# ET-POWER.net
KiCad netlist of a schematic drawn in Altium Designer
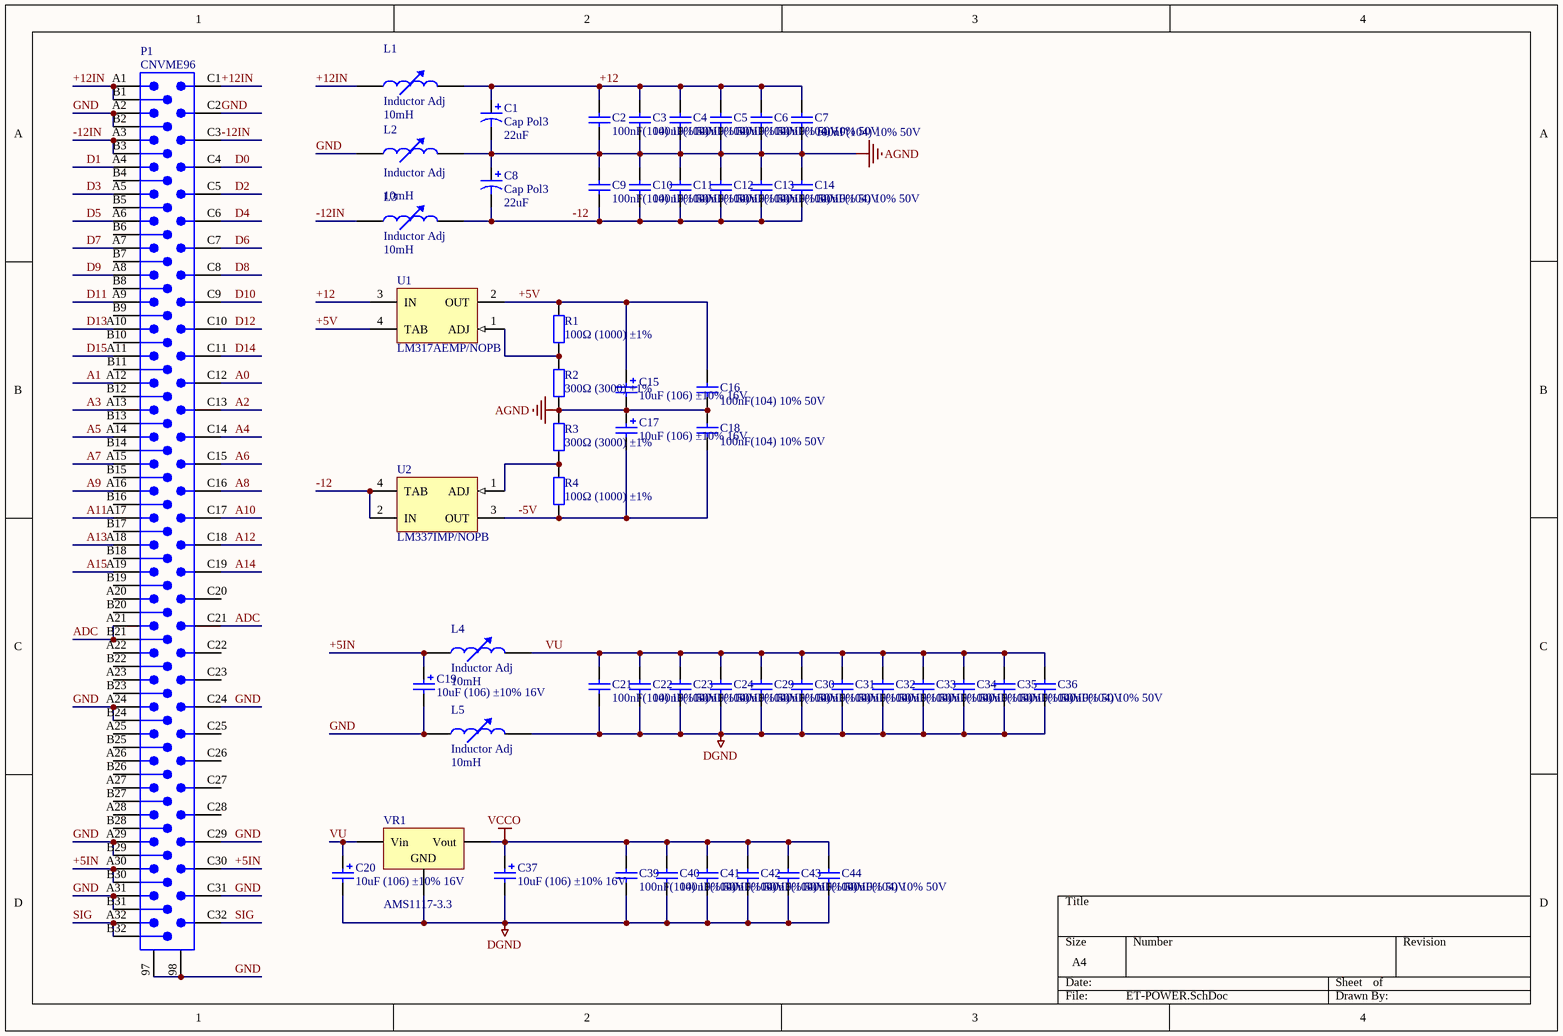
[diagram p0: ET-POWER.SchDoc]

(export (version "E")
  (design (tool "Eeschema 10.0.6"))
  (components
    (comp (ref "C1")
      (value "Cap Pol3")
      (footprint "2220")
      (description "Polarized Capacitor (Surface Mount)")
      (fields (field (name "ALTIUM_VALUE") "22uF") (field (name "PUBLISHER") "Altium Limited"))
      (libsource (lib "Miscellaneous Devices") (part "Cap Pol3"))
    )
    (comp (ref "C2")
      (value "100nF(104) 10% 50V")
      (footprint "LC-0805_C")
      (description "贴片电容")
      (libsource (lib "Miscellaneous Devices LC") (part "0805 100nF(104) 10% 50V"))
    )
    (comp (ref "C3")
      (value "100nF(104) 10% 50V")
      (footprint "LC-0805_C")
      (description "贴片电容")
      (libsource (lib "Miscellaneous Devices LC") (part "0805 100nF(104) 10% 50V"))
    )
    (comp (ref "C4")
      (value "100nF(104) 10% 50V")
      (footprint "LC-0805_C")
      (description "贴片电容")
      (libsource (lib "Miscellaneous Devices LC") (part "0805 100nF(104) 10% 50V"))
    )
    (comp (ref "C5")
      (value "100nF(104) 10% 50V")
      (footprint "LC-0805_C")
      (description "贴片电容")
      (libsource (lib "Miscellaneous Devices LC") (part "0805 100nF(104) 10% 50V"))
    )
    (comp (ref "C6")
      (value "100nF(104) 10% 50V")
      (footprint "LC-0805_C")
      (description "贴片电容")
      (libsource (lib "Miscellaneous Devices LC") (part "0805 100nF(104) 10% 50V"))
    )
    (comp (ref "C7")
      (value "100nF(104) 10% 50V")
      (footprint "LC-0805_C")
      (description "贴片电容")
      (libsource (lib "Miscellaneous Devices LC") (part "0805 100nF(104) 10% 50V"))
    )
    (comp (ref "C8")
      (value "Cap Pol3")
      (footprint "2220")
      (description "Polarized Capacitor (Surface Mount)")
      (fields (field (name "ALTIUM_VALUE") "22uF") (field (name "PUBLISHER") "Altium Limited"))
      (libsource (lib "Miscellaneous Devices") (part "Cap Pol3"))
    )
    (comp (ref "C9")
      (value "100nF(104) 10% 50V")
      (footprint "LC-0805_C")
      (description "贴片电容")
      (libsource (lib "Miscellaneous Devices LC") (part "0805 100nF(104) 10% 50V"))
    )
    (comp (ref "C10")
      (value "100nF(104) 10% 50V")
      (footprint "LC-0805_C")
      (description "贴片电容")
      (libsource (lib "Miscellaneous Devices LC") (part "0805 100nF(104) 10% 50V"))
    )
    (comp (ref "C11")
      (value "100nF(104) 10% 50V")
      (footprint "LC-0805_C")
      (description "贴片电容")
      (libsource (lib "Miscellaneous Devices LC") (part "0805 100nF(104) 10% 50V"))
    )
    (comp (ref "C12")
      (value "100nF(104) 10% 50V")
      (footprint "LC-0805_C")
      (description "贴片电容")
      (libsource (lib "Miscellaneous Devices LC") (part "0805 100nF(104) 10% 50V"))
    )
    (comp (ref "C13")
      (value "100nF(104) 10% 50V")
      (footprint "LC-0805_C")
      (description "贴片电容")
      (libsource (lib "Miscellaneous Devices LC") (part "0805 100nF(104) 10% 50V"))
    )
    (comp (ref "C14")
      (value "100nF(104) 10% 50V")
      (footprint "LC-0805_C")
      (description "贴片电容")
      (libsource (lib "Miscellaneous Devices LC") (part "0805 100nF(104) 10% 50V"))
    )
    (comp (ref "C15")
      (value "10uF (106) ±10% 16V")
      (footprint "LC-CASE-A_3216")
      (description "钽电容")
      (libsource (lib "Miscellaneous Devices LC") (part "3216 10uF (106) 10% 16V"))
    )
    (comp (ref "C16")
      (value "100nF(104) 10% 50V")
      (footprint "LC-0805_C")
      (description "贴片电容")
      (libsource (lib "Miscellaneous Devices LC") (part "0805 100nF(104) 10% 50V"))
    )
    (comp (ref "C17")
      (value "10uF (106) ±10% 16V")
      (footprint "LC-CASE-A_3216")
      (description "钽电容")
      (libsource (lib "Miscellaneous Devices LC") (part "3216 10uF (106) 10% 16V"))
    )
    (comp (ref "C18")
      (value "100nF(104) 10% 50V")
      (footprint "LC-0805_C")
      (description "贴片电容")
      (libsource (lib "Miscellaneous Devices LC") (part "0805 100nF(104) 10% 50V"))
    )
    (comp (ref "C19")
      (value "10uF (106) ±10% 16V")
      (footprint "LC-CASE-A_3216")
      (description "钽电容")
      (libsource (lib "Miscellaneous Devices LC") (part "3216 10uF (106) 10% 16V"))
    )
    (comp (ref "C20")
      (value "10uF (106) ±10% 16V")
      (footprint "LC-CASE-A_3216")
      (description "钽电容")
      (libsource (lib "Miscellaneous Devices LC") (part "3216 10uF (106) 10% 16V"))
    )
    (comp (ref "C21")
      (value "100nF(104) 10% 50V")
      (footprint "LC-0805_C")
      (description "贴片电容")
      (libsource (lib "Miscellaneous Devices LC") (part "0805 100nF(104) 10% 50V"))
    )
    (comp (ref "C22")
      (value "100nF(104) 10% 50V")
      (footprint "LC-0805_C")
      (description "贴片电容")
      (libsource (lib "Miscellaneous Devices LC") (part "0805 100nF(104) 10% 50V"))
    )
    (comp (ref "C23")
      (value "100nF(104) 10% 50V")
      (footprint "LC-0805_C")
      (description "贴片电容")
      (libsource (lib "Miscellaneous Devices LC") (part "0805 100nF(104) 10% 50V"))
    )
    (comp (ref "C24")
      (value "100nF(104) 10% 50V")
      (footprint "LC-0805_C")
      (description "贴片电容")
      (libsource (lib "Miscellaneous Devices LC") (part "0805 100nF(104) 10% 50V"))
    )
    (comp (ref "C29")
      (value "100nF(104) 10% 50V")
      (footprint "LC-0805_C")
      (description "贴片电容")
      (libsource (lib "Miscellaneous Devices LC") (part "0805 100nF(104) 10% 50V"))
    )
    (comp (ref "C30")
      (value "100nF(104) 10% 50V")
      (footprint "LC-0805_C")
      (description "贴片电容")
      (libsource (lib "Miscellaneous Devices LC") (part "0805 100nF(104) 10% 50V"))
    )
    (comp (ref "C31")
      (value "100nF(104) 10% 50V")
      (footprint "LC-0805_C")
      (description "贴片电容")
      (libsource (lib "Miscellaneous Devices LC") (part "0805 100nF(104) 10% 50V"))
    )
    (comp (ref "C32")
      (value "100nF(104) 10% 50V")
      (footprint "LC-0805_C")
      (description "贴片电容")
      (libsource (lib "Miscellaneous Devices LC") (part "0805 100nF(104) 10% 50V"))
    )
    (comp (ref "C33")
      (value "100nF(104) 10% 50V")
      (footprint "LC-0805_C")
      (description "贴片电容")
      (libsource (lib "Miscellaneous Devices LC") (part "0805 100nF(104) 10% 50V"))
    )
    (comp (ref "C34")
      (value "100nF(104) 10% 50V")
      (footprint "LC-0805_C")
      (description "贴片电容")
      (libsource (lib "Miscellaneous Devices LC") (part "0805 100nF(104) 10% 50V"))
    )
    (comp (ref "C35")
      (value "100nF(104) 10% 50V")
      (footprint "LC-0805_C")
      (description "贴片电容")
      (libsource (lib "Miscellaneous Devices LC") (part "0805 100nF(104) 10% 50V"))
    )
    (comp (ref "C36")
      (value "100nF(104) 10% 50V")
      (footprint "LC-0805_C")
      (description "贴片电容")
      (libsource (lib "Miscellaneous Devices LC") (part "0805 100nF(104) 10% 50V"))
    )
    (comp (ref "C37")
      (value "10uF (106) ±10% 16V")
      (footprint "LC-CASE-A_3216")
      (description "钽电容")
      (libsource (lib "Miscellaneous Devices LC") (part "3216 10uF (106) 10% 16V"))
    )
    (comp (ref "C39")
      (value "100nF(104) 10% 50V")
      (footprint "LC-0805_C")
      (description "贴片电容")
      (libsource (lib "Miscellaneous Devices LC") (part "0805 100nF(104) 10% 50V"))
    )
    (comp (ref "C40")
      (value "100nF(104) 10% 50V")
      (footprint "LC-0805_C")
      (description "贴片电容")
      (libsource (lib "Miscellaneous Devices LC") (part "0805 100nF(104) 10% 50V"))
    )
    (comp (ref "C41")
      (value "100nF(104) 10% 50V")
      (footprint "LC-0805_C")
      (description "贴片电容")
      (libsource (lib "Miscellaneous Devices LC") (part "0805 100nF(104) 10% 50V"))
    )
    (comp (ref "C42")
      (value "100nF(104) 10% 50V")
      (footprint "LC-0805_C")
      (description "贴片电容")
      (libsource (lib "Miscellaneous Devices LC") (part "0805 100nF(104) 10% 50V"))
    )
    (comp (ref "C43")
      (value "100nF(104) 10% 50V")
      (footprint "LC-0805_C")
      (description "贴片电容")
      (libsource (lib "Miscellaneous Devices LC") (part "0805 100nF(104) 10% 50V"))
    )
    (comp (ref "C44")
      (value "100nF(104) 10% 50V")
      (footprint "LC-0805_C")
      (description "贴片电容")
      (libsource (lib "Miscellaneous Devices LC") (part "0805 100nF(104) 10% 50V"))
    )
    (comp (ref "L1")
      (value "Inductor Adj")
      (footprint "AXIAL-0.4")
      (description "Adjustable Inductor")
      (fields (field (name "ALTIUM_VALUE") "10mH") (field (name "PUBLISHER") "Altium Limited"))
      (libsource (lib "Miscellaneous Devices") (part "Inductor Adj"))
    )
    (comp (ref "L2")
      (value "Inductor Adj")
      (footprint "AXIAL-0.4")
      (description "Adjustable Inductor")
      (fields (field (name "ALTIUM_VALUE") "10mH") (field (name "PUBLISHER") "Altium Limited"))
      (libsource (lib "Miscellaneous Devices") (part "Inductor Adj"))
    )
    (comp (ref "L3")
      (value "Inductor Adj")
      (footprint "AXIAL-0.4")
      (description "Adjustable Inductor")
      (fields (field (name "ALTIUM_VALUE") "10mH") (field (name "PUBLISHER") "Altium Limited"))
      (libsource (lib "Miscellaneous Devices") (part "Inductor Adj"))
    )
    (comp (ref "L4")
      (value "Inductor Adj")
      (footprint "AXIAL-0.4")
      (description "Adjustable Inductor")
      (fields (field (name "ALTIUM_VALUE") "10mH") (field (name "PUBLISHER") "Altium Limited"))
      (libsource (lib "Miscellaneous Devices") (part "Inductor Adj"))
    )
    (comp (ref "L5")
      (value "Inductor Adj")
      (footprint "AXIAL-0.4")
      (description "Adjustable Inductor")
      (fields (field (name "ALTIUM_VALUE") "10mH") (field (name "PUBLISHER") "Altium Limited"))
      (libsource (lib "Miscellaneous Devices") (part "Inductor Adj"))
    )
    (comp (ref "P1")
      (value "CNVME96")
      (footprint "mini-ET:CNVME96")
      (description "96-Pin Connector (3x32 2.54mm grid)")
      (libsource (lib "*") (part "CNVME96"))
    )
    (comp (ref "R1")
      (value "100Ω (1000) ±1%")
      (footprint "LC-0805_R")
      (description "贴片电阻")
      (libsource (lib "Miscellaneous Devices LC") (part "0805 100Ω (1000) 1%"))
    )
    (comp (ref "R2")
      (value "300Ω (3000) ±1%")
      (footprint "LC-0805_R")
      (description "贴片电阻")
      (libsource (lib "Miscellaneous Devices LC") (part "0805 300Ω (3000) 1%"))
    )
    (comp (ref "R3")
      (value "300Ω (3000) ±1%")
      (footprint "LC-0805_R")
      (description "贴片电阻")
      (libsource (lib "Miscellaneous Devices LC") (part "0805 300Ω (3000) 1%"))
    )
    (comp (ref "R4")
      (value "100Ω (1000) ±1%")
      (footprint "LC-0805_R")
      (description "贴片电阻")
      (libsource (lib "Miscellaneous Devices LC") (part "0805 100Ω (1000) 1%"))
    )
    (comp (ref "U1")
      (value "LM317AEMP/NOPB")
      (footprint "mini-ET:MP04A_N")
      (description "3-Terminal Adjustable Regulator, 4-pin SOT-223, Pb-Free")
      (fields (field (name "MANUFACTURER") "National Semiconductor"))
      (libsource (lib "National Semiconductor LDO") (part "LM317AEMP/NOPB"))
    )
    (comp (ref "U2")
      (value "LM337IMP/NOPB")
      (footprint "mini-ET:MP04A_N")
      (description "3-Terminal Adjustable Negative Regulator, 4-pin SOT-223, Pb-Free")
      (fields
        (field (name "MANUFACTURER") "National Semiconductor")
        (field (name "PUBLISHER") "Altium Limited")
      )
      (libsource (lib "NSC LDO") (part "LM337IMP/NOPB"))
    )
    (comp (ref "VR1")
      (value "AMS1117-3.3")
      (footprint "LC-SOT-223")
      (description "低压差线性稳压(LDO)")
      (libsource (lib "Miscellaneous Devices LC") (part "SOT-223 AMS1117-3.3"))
    )
  )
  (nets
    (net (code "1") (name "/+5IN") (class "Default")
      (node (ref "C19") (pin "1") (pinfunction "1_1") (pintype "passive"))
      (node (ref "L4") (pin "1") (pinfunction "1_1") (pintype "passive"))
      (node (ref "P1") (pin "A30") (pinfunction "A30_A30") (pintype "passive"))
      (node (ref "P1") (pin "B30") (pinfunction "B30_B30") (pintype "passive"))
      (node (ref "P1") (pin "C30") (pinfunction "C30_C30") (pintype "passive"))
    )
    (net (code "2") (name "/+5V") (class "Default")
      (node (ref "C15") (pin "1") (pinfunction "1_1") (pintype "passive"))
      (node (ref "C16") (pin "2") (pinfunction "2_2") (pintype "passive"))
      (node (ref "R1") (pin "2") (pinfunction "2_2") (pintype "passive"))
      (node (ref "U1") (pin "2") (pinfunction "OUT_2") (pintype "power_in"))
      (node (ref "U1") (pin "4") (pinfunction "TAB_4") (pintype "power_in"))
    )
    (net (code "3") (name "/+12") (class "Default")
      (node (ref "C1") (pin "1") (pinfunction "1_1") (pintype "passive"))
      (node (ref "C2") (pin "2") (pinfunction "2_2") (pintype "passive"))
      (node (ref "C3") (pin "2") (pinfunction "2_2") (pintype "passive"))
      (node (ref "C4") (pin "2") (pinfunction "2_2") (pintype "passive"))
      (node (ref "C5") (pin "2") (pinfunction "2_2") (pintype "passive"))
      (node (ref "C6") (pin "2") (pinfunction "2_2") (pintype "passive"))
      (node (ref "C7") (pin "2") (pinfunction "2_2") (pintype "passive"))
      (node (ref "L1") (pin "2") (pinfunction "2_2") (pintype "passive"))
      (node (ref "U1") (pin "3") (pinfunction "IN_3") (pintype "power_in"))
    )
    (net (code "4") (name "/+12IN") (class "Default")
      (node (ref "L1") (pin "1") (pinfunction "1_1") (pintype "passive"))
      (node (ref "P1") (pin "A1") (pinfunction "A1_A1") (pintype "passive"))
      (node (ref "P1") (pin "B1") (pinfunction "B1_B1") (pintype "passive"))
      (node (ref "P1") (pin "C1") (pinfunction "C1_C1") (pintype "passive"))
    )
    (net (code "5") (name "/-5V") (class "Default")
      (node (ref "C17") (pin "2") (pinfunction "2_2") (pintype "passive"))
      (node (ref "C18") (pin "1") (pinfunction "1_1") (pintype "passive"))
      (node (ref "R4") (pin "1") (pinfunction "1_1") (pintype "passive"))
      (node (ref "U2") (pin "3") (pinfunction "OUT_3") (pintype "power_in"))
    )
    (net (code "6") (name "/-12") (class "Default")
      (node (ref "C10") (pin "1") (pinfunction "1_1") (pintype "passive"))
      (node (ref "C11") (pin "1") (pinfunction "1_1") (pintype "passive"))
      (node (ref "C12") (pin "1") (pinfunction "1_1") (pintype "passive"))
      (node (ref "C13") (pin "1") (pinfunction "1_1") (pintype "passive"))
      (node (ref "C14") (pin "1") (pinfunction "1_1") (pintype "passive"))
      (node (ref "C8") (pin "2") (pinfunction "2_2") (pintype "passive"))
      (node (ref "C9") (pin "1") (pinfunction "1_1") (pintype "passive"))
      (node (ref "L3") (pin "2") (pinfunction "2_2") (pintype "passive"))
      (node (ref "U2") (pin "2") (pinfunction "IN_2") (pintype "power_in"))
      (node (ref "U2") (pin "4") (pinfunction "TAB_4") (pintype "power_in"))
    )
    (net (code "7") (name "/-12IN") (class "Default")
      (node (ref "L3") (pin "1") (pinfunction "1_1") (pintype "passive"))
      (node (ref "P1") (pin "A3") (pinfunction "A3_A3") (pintype "passive"))
      (node (ref "P1") (pin "B3") (pinfunction "B3_B3") (pintype "passive"))
      (node (ref "P1") (pin "C3") (pinfunction "C3_C3") (pintype "passive"))
    )
    (net (code "8") (name "/A0") (class "Default")
      (node (ref "P1") (pin "C12") (pinfunction "C12_C12") (pintype "passive"))
    )
    (net (code "9") (name "/A1") (class "Default")
      (node (ref "P1") (pin "A12") (pinfunction "A12_A12") (pintype "passive"))
    )
    (net (code "10") (name "/A2") (class "Default")
      (node (ref "P1") (pin "C13") (pinfunction "C13_C13") (pintype "passive"))
    )
    (net (code "11") (name "/A3") (class "Default")
      (node (ref "P1") (pin "A13") (pinfunction "A13_A13") (pintype "passive"))
    )
    (net (code "12") (name "/A4") (class "Default")
      (node (ref "P1") (pin "C14") (pinfunction "C14_C14") (pintype "passive"))
    )
    (net (code "13") (name "/A5") (class "Default")
      (node (ref "P1") (pin "A14") (pinfunction "A14_A14") (pintype "passive"))
    )
    (net (code "14") (name "/A6") (class "Default")
      (node (ref "P1") (pin "C15") (pinfunction "C15_C15") (pintype "passive"))
    )
    (net (code "15") (name "/A7") (class "Default")
      (node (ref "P1") (pin "A15") (pinfunction "A15_A15") (pintype "passive"))
    )
    (net (code "16") (name "/A8") (class "Default")
      (node (ref "P1") (pin "C16") (pinfunction "C16_C16") (pintype "passive"))
    )
    (net (code "17") (name "/A9") (class "Default")
      (node (ref "P1") (pin "A16") (pinfunction "A16_A16") (pintype "passive"))
    )
    (net (code "18") (name "/A10") (class "Default")
      (node (ref "P1") (pin "C17") (pinfunction "C17_C17") (pintype "passive"))
    )
    (net (code "19") (name "/A11") (class "Default")
      (node (ref "P1") (pin "A17") (pinfunction "A17_A17") (pintype "passive"))
    )
    (net (code "20") (name "/A12") (class "Default")
      (node (ref "P1") (pin "C18") (pinfunction "C18_C18") (pintype "passive"))
    )
    (net (code "21") (name "/A13") (class "Default")
      (node (ref "P1") (pin "A18") (pinfunction "A18_A18") (pintype "passive"))
    )
    (net (code "22") (name "/A14") (class "Default")
      (node (ref "P1") (pin "C19") (pinfunction "C19_C19") (pintype "passive"))
    )
    (net (code "23") (name "/A15") (class "Default")
      (node (ref "P1") (pin "A19") (pinfunction "A19_A19") (pintype "passive"))
    )
    (net (code "24") (name "/ADC") (class "Default")
      (node (ref "P1") (pin "A21") (pinfunction "A21_A21") (pintype "passive"))
      (node (ref "P1") (pin "B21") (pinfunction "B21_B21") (pintype "passive"))
      (node (ref "P1") (pin "C21") (pinfunction "C21_C21") (pintype "passive"))
    )
    (net (code "25") (name "/D0") (class "Default")
      (node (ref "P1") (pin "C4") (pinfunction "C4_C4") (pintype "passive"))
    )
    (net (code "26") (name "/D1") (class "Default")
      (node (ref "P1") (pin "A4") (pinfunction "A4_A4") (pintype "passive"))
    )
    (net (code "27") (name "/D2") (class "Default")
      (node (ref "P1") (pin "C5") (pinfunction "C5_C5") (pintype "passive"))
    )
    (net (code "28") (name "/D3") (class "Default")
      (node (ref "P1") (pin "A5") (pinfunction "A5_A5") (pintype "passive"))
    )
    (net (code "29") (name "/D4") (class "Default")
      (node (ref "P1") (pin "C6") (pinfunction "C6_C6") (pintype "passive"))
    )
    (net (code "30") (name "/D5") (class "Default")
      (node (ref "P1") (pin "A6") (pinfunction "A6_A6") (pintype "passive"))
    )
    (net (code "31") (name "/D6") (class "Default")
      (node (ref "P1") (pin "C7") (pinfunction "C7_C7") (pintype "passive"))
    )
    (net (code "32") (name "/D7") (class "Default")
      (node (ref "P1") (pin "A7") (pinfunction "A7_A7") (pintype "passive"))
    )
    (net (code "33") (name "/D8") (class "Default")
      (node (ref "P1") (pin "C8") (pinfunction "C8_C8") (pintype "passive"))
    )
    (net (code "34") (name "/D9") (class "Default")
      (node (ref "P1") (pin "A8") (pinfunction "A8_A8") (pintype "passive"))
    )
    (net (code "35") (name "/D10") (class "Default")
      (node (ref "P1") (pin "C9") (pinfunction "C9_C9") (pintype "passive"))
    )
    (net (code "36") (name "/D11") (class "Default")
      (node (ref "P1") (pin "A9") (pinfunction "A9_A9") (pintype "passive"))
    )
    (net (code "37") (name "/D12") (class "Default")
      (node (ref "P1") (pin "C10") (pinfunction "C10_C10") (pintype "passive"))
    )
    (net (code "38") (name "/D13") (class "Default")
      (node (ref "P1") (pin "A10") (pinfunction "A10_A10") (pintype "passive"))
    )
    (net (code "39") (name "/D14") (class "Default")
      (node (ref "P1") (pin "C11") (pinfunction "C11_C11") (pintype "passive"))
    )
    (net (code "40") (name "/D15") (class "Default")
      (node (ref "P1") (pin "A11") (pinfunction "A11_A11") (pintype "passive"))
    )
    (net (code "41") (name "/GND") (class "Default")
      (node (ref "C19") (pin "2") (pinfunction "2_2") (pintype "passive"))
      (node (ref "L2") (pin "1") (pinfunction "1_1") (pintype "passive"))
      (node (ref "L5") (pin "1") (pinfunction "1_1") (pintype "passive"))
      (node (ref "P1") (pin "97") (pinfunction "97_97") (pintype "passive"))
      (node (ref "P1") (pin "98") (pinfunction "98_98") (pintype "passive"))
      (node (ref "P1") (pin "A2") (pinfunction "A2_A2") (pintype "passive"))
      (node (ref "P1") (pin "A24") (pinfunction "A24_A24") (pintype "passive"))
      (node (ref "P1") (pin "A29") (pinfunction "A29_A29") (pintype "passive"))
      (node (ref "P1") (pin "A31") (pinfunction "A31_A31") (pintype "passive"))
      (node (ref "P1") (pin "B2") (pinfunction "B2_B2") (pintype "passive"))
      (node (ref "P1") (pin "B24") (pinfunction "B24_B24") (pintype "passive"))
      (node (ref "P1") (pin "B29") (pinfunction "B29_B29") (pintype "passive"))
      (node (ref "P1") (pin "B31") (pinfunction "B31_B31") (pintype "passive"))
      (node (ref "P1") (pin "C2") (pinfunction "C2_C2") (pintype "passive"))
      (node (ref "P1") (pin "C24") (pinfunction "C24_C24") (pintype "passive"))
      (node (ref "P1") (pin "C29") (pinfunction "C29_C29") (pintype "passive"))
      (node (ref "P1") (pin "C31") (pinfunction "C31_C31") (pintype "passive"))
    )
    (net (code "42") (name "/SIG") (class "Default")
      (node (ref "P1") (pin "A32") (pinfunction "A32_A32") (pintype "passive"))
      (node (ref "P1") (pin "B32") (pinfunction "B32_B32") (pintype "passive"))
      (node (ref "P1") (pin "C32") (pinfunction "C32_C32") (pintype "passive"))
    )
    (net (code "43") (name "/VU") (class "Default")
      (node (ref "C20") (pin "1") (pinfunction "1_1") (pintype "passive"))
      (node (ref "C21") (pin "2") (pinfunction "2_2") (pintype "passive"))
      (node (ref "C22") (pin "2") (pinfunction "2_2") (pintype "passive"))
      (node (ref "C23") (pin "2") (pinfunction "2_2") (pintype "passive"))
      (node (ref "C24") (pin "2") (pinfunction "2_2") (pintype "passive"))
      (node (ref "C29") (pin "2") (pinfunction "2_2") (pintype "passive"))
      (node (ref "C30") (pin "2") (pinfunction "2_2") (pintype "passive"))
      (node (ref "C31") (pin "2") (pinfunction "2_2") (pintype "passive"))
      (node (ref "C32") (pin "2") (pinfunction "2_2") (pintype "passive"))
      (node (ref "C33") (pin "2") (pinfunction "2_2") (pintype "passive"))
      (node (ref "C34") (pin "2") (pinfunction "2_2") (pintype "passive"))
      (node (ref "C35") (pin "2") (pinfunction "2_2") (pintype "passive"))
      (node (ref "C36") (pin "2") (pinfunction "2_2") (pintype "passive"))
      (node (ref "L4") (pin "2") (pinfunction "2_2") (pintype "passive"))
      (node (ref "VR1") (pin "3") (pinfunction "Vin_3") (pintype "passive"))
    )
    (net (code "44") (name "AGND") (class "Default")
      (node (ref "C1") (pin "2") (pinfunction "2_2") (pintype "passive"))
      (node (ref "C10") (pin "2") (pinfunction "2_2") (pintype "passive"))
      (node (ref "C11") (pin "2") (pinfunction "2_2") (pintype "passive"))
      (node (ref "C12") (pin "2") (pinfunction "2_2") (pintype "passive"))
      (node (ref "C13") (pin "2") (pinfunction "2_2") (pintype "passive"))
      (node (ref "C14") (pin "2") (pinfunction "2_2") (pintype "passive"))
      (node (ref "C15") (pin "2") (pinfunction "2_2") (pintype "passive"))
      (node (ref "C16") (pin "1") (pinfunction "1_1") (pintype "passive"))
      (node (ref "C17") (pin "1") (pinfunction "1_1") (pintype "passive"))
      (node (ref "C18") (pin "2") (pinfunction "2_2") (pintype "passive"))
      (node (ref "C2") (pin "1") (pinfunction "1_1") (pintype "passive"))
      (node (ref "C3") (pin "1") (pinfunction "1_1") (pintype "passive"))
      (node (ref "C4") (pin "1") (pinfunction "1_1") (pintype "passive"))
      (node (ref "C5") (pin "1") (pinfunction "1_1") (pintype "passive"))
      (node (ref "C6") (pin "1") (pinfunction "1_1") (pintype "passive"))
      (node (ref "C7") (pin "1") (pinfunction "1_1") (pintype "passive"))
      (node (ref "C8") (pin "1") (pinfunction "1_1") (pintype "passive"))
      (node (ref "C9") (pin "2") (pinfunction "2_2") (pintype "passive"))
      (node (ref "L2") (pin "2") (pinfunction "2_2") (pintype "passive"))
      (node (ref "R2") (pin "1") (pinfunction "1_1") (pintype "passive"))
      (node (ref "R3") (pin "2") (pinfunction "2_2") (pintype "passive"))
    )
    (net (code "45") (name "DGND") (class "Default")
      (node (ref "C20") (pin "2") (pinfunction "2_2") (pintype "passive"))
      (node (ref "C21") (pin "1") (pinfunction "1_1") (pintype "passive"))
      (node (ref "C22") (pin "1") (pinfunction "1_1") (pintype "passive"))
      (node (ref "C23") (pin "1") (pinfunction "1_1") (pintype "passive"))
      (node (ref "C24") (pin "1") (pinfunction "1_1") (pintype "passive"))
      (node (ref "C29") (pin "1") (pinfunction "1_1") (pintype "passive"))
      (node (ref "C30") (pin "1") (pinfunction "1_1") (pintype "passive"))
      (node (ref "C31") (pin "1") (pinfunction "1_1") (pintype "passive"))
      (node (ref "C32") (pin "1") (pinfunction "1_1") (pintype "passive"))
      (node (ref "C33") (pin "1") (pinfunction "1_1") (pintype "passive"))
      (node (ref "C34") (pin "1") (pinfunction "1_1") (pintype "passive"))
      (node (ref "C35") (pin "1") (pinfunction "1_1") (pintype "passive"))
      (node (ref "C36") (pin "1") (pinfunction "1_1") (pintype "passive"))
      (node (ref "C37") (pin "2") (pinfunction "2_2") (pintype "passive"))
      (node (ref "C39") (pin "1") (pinfunction "1_1") (pintype "passive"))
      (node (ref "C40") (pin "1") (pinfunction "1_1") (pintype "passive"))
      (node (ref "C41") (pin "1") (pinfunction "1_1") (pintype "passive"))
      (node (ref "C42") (pin "1") (pinfunction "1_1") (pintype "passive"))
      (node (ref "C43") (pin "1") (pinfunction "1_1") (pintype "passive"))
      (node (ref "C44") (pin "1") (pinfunction "1_1") (pintype "passive"))
      (node (ref "L5") (pin "2") (pinfunction "2_2") (pintype "passive"))
      (node (ref "VR1") (pin "1") (pinfunction "GND_1") (pintype "passive"))
    )
    (net (code "46") (name "Net-(U1-ADJ)") (class "Default")
      (node (ref "R1") (pin "1") (pinfunction "1_1") (pintype "passive"))
      (node (ref "R2") (pin "2") (pinfunction "2_2") (pintype "passive"))
      (node (ref "U1") (pin "1") (pinfunction "ADJ_1") (pintype "input"))
    )
    (net (code "47") (name "Net-(U2-ADJ)") (class "Default")
      (node (ref "R3") (pin "1") (pinfunction "1_1") (pintype "passive"))
      (node (ref "R4") (pin "2") (pinfunction "2_2") (pintype "passive"))
      (node (ref "U2") (pin "1") (pinfunction "ADJ_1") (pintype "input"))
    )
    (net (code "48") (name "VCCO") (class "Default")
      (node (ref "C37") (pin "1") (pinfunction "1_1") (pintype "passive"))
      (node (ref "C39") (pin "2") (pinfunction "2_2") (pintype "passive"))
      (node (ref "C40") (pin "2") (pinfunction "2_2") (pintype "passive"))
      (node (ref "C41") (pin "2") (pinfunction "2_2") (pintype "passive"))
      (node (ref "C42") (pin "2") (pinfunction "2_2") (pintype "passive"))
      (node (ref "C43") (pin "2") (pinfunction "2_2") (pintype "passive"))
      (node (ref "C44") (pin "2") (pinfunction "2_2") (pintype "passive"))
      (node (ref "VR1") (pin "2") (pinfunction "Vout_2") (pintype "passive"))
    )
    (net (code "49") (name "unconnected-(P1-PadA20)") (class "Default")
      (node (ref "P1") (pin "A20") (pinfunction "A20_A20") (pintype "passive"))
    )
    (net (code "50") (name "unconnected-(P1-PadA22)") (class "Default")
      (node (ref "P1") (pin "A22") (pinfunction "A22_A22") (pintype "passive"))
    )
    (net (code "51") (name "unconnected-(P1-PadA23)") (class "Default")
      (node (ref "P1") (pin "A23") (pinfunction "A23_A23") (pintype "passive"))
    )
    (net (code "52") (name "unconnected-(P1-PadA25)") (class "Default")
      (node (ref "P1") (pin "A25") (pinfunction "A25_A25") (pintype "passive"))
    )
    (net (code "53") (name "unconnected-(P1-PadA26)") (class "Default")
      (node (ref "P1") (pin "A26") (pinfunction "A26_A26") (pintype "passive"))
    )
    (net (code "54") (name "unconnected-(P1-PadA27)") (class "Default")
      (node (ref "P1") (pin "A27") (pinfunction "A27_A27") (pintype "passive"))
    )
    (net (code "55") (name "unconnected-(P1-PadA28)") (class "Default")
      (node (ref "P1") (pin "A28") (pinfunction "A28_A28") (pintype "passive"))
    )
    (net (code "56") (name "unconnected-(P1-PadB4)") (class "Default")
      (node (ref "P1") (pin "B4") (pinfunction "B4_B4") (pintype "passive"))
    )
    (net (code "57") (name "unconnected-(P1-PadB5)") (class "Default")
      (node (ref "P1") (pin "B5") (pinfunction "B5_B5") (pintype "passive"))
    )
    (net (code "58") (name "unconnected-(P1-PadB6)") (class "Default")
      (node (ref "P1") (pin "B6") (pinfunction "B6_B6") (pintype "passive"))
    )
    (net (code "59") (name "unconnected-(P1-PadB7)") (class "Default")
      (node (ref "P1") (pin "B7") (pinfunction "B7_B7") (pintype "passive"))
    )
    (net (code "60") (name "unconnected-(P1-PadB8)") (class "Default")
      (node (ref "P1") (pin "B8") (pinfunction "B8_B8") (pintype "passive"))
    )
    (net (code "61") (name "unconnected-(P1-PadB9)") (class "Default")
      (node (ref "P1") (pin "B9") (pinfunction "B9_B9") (pintype "passive"))
    )
    (net (code "62") (name "unconnected-(P1-PadB10)") (class "Default")
      (node (ref "P1") (pin "B10") (pinfunction "B10_B10") (pintype "passive"))
    )
    (net (code "63") (name "unconnected-(P1-PadB11)") (class "Default")
      (node (ref "P1") (pin "B11") (pinfunction "B11_B11") (pintype "passive"))
    )
    (net (code "64") (name "unconnected-(P1-PadB12)") (class "Default")
      (node (ref "P1") (pin "B12") (pinfunction "B12_B12") (pintype "passive"))
    )
    (net (code "65") (name "unconnected-(P1-PadB13)") (class "Default")
      (node (ref "P1") (pin "B13") (pinfunction "B13_B13") (pintype "passive"))
    )
    (net (code "66") (name "unconnected-(P1-PadB14)") (class "Default")
      (node (ref "P1") (pin "B14") (pinfunction "B14_B14") (pintype "passive"))
    )
    (net (code "67") (name "unconnected-(P1-PadB15)") (class "Default")
      (node (ref "P1") (pin "B15") (pinfunction "B15_B15") (pintype "passive"))
    )
    (net (code "68") (name "unconnected-(P1-PadB16)") (class "Default")
      (node (ref "P1") (pin "B16") (pinfunction "B16_B16") (pintype "passive"))
    )
    (net (code "69") (name "unconnected-(P1-PadB17)") (class "Default")
      (node (ref "P1") (pin "B17") (pinfunction "B17_B17") (pintype "passive"))
    )
    (net (code "70") (name "unconnected-(P1-PadB18)") (class "Default")
      (node (ref "P1") (pin "B18") (pinfunction "B18_B18") (pintype "passive"))
    )
    (net (code "71") (name "unconnected-(P1-PadB19)") (class "Default")
      (node (ref "P1") (pin "B19") (pinfunction "B19_B19") (pintype "passive"))
    )
    (net (code "72") (name "unconnected-(P1-PadB20)") (class "Default")
      (node (ref "P1") (pin "B20") (pinfunction "B20_B20") (pintype "passive"))
    )
    (net (code "73") (name "unconnected-(P1-PadB22)") (class "Default")
      (node (ref "P1") (pin "B22") (pinfunction "B22_B22") (pintype "passive"))
    )
    (net (code "74") (name "unconnected-(P1-PadB23)") (class "Default")
      (node (ref "P1") (pin "B23") (pinfunction "B23_B23") (pintype "passive"))
    )
    (net (code "75") (name "unconnected-(P1-PadB25)") (class "Default")
      (node (ref "P1") (pin "B25") (pinfunction "B25_B25") (pintype "passive"))
    )
    (net (code "76") (name "unconnected-(P1-PadB26)") (class "Default")
      (node (ref "P1") (pin "B26") (pinfunction "B26_B26") (pintype "passive"))
    )
    (net (code "77") (name "unconnected-(P1-PadB27)") (class "Default")
      (node (ref "P1") (pin "B27") (pinfunction "B27_B27") (pintype "passive"))
    )
    (net (code "78") (name "unconnected-(P1-PadB28)") (class "Default")
      (node (ref "P1") (pin "B28") (pinfunction "B28_B28") (pintype "passive"))
    )
    (net (code "79") (name "unconnected-(P1-PadC20)") (class "Default")
      (node (ref "P1") (pin "C20") (pinfunction "C20_C20") (pintype "passive"))
    )
    (net (code "80") (name "unconnected-(P1-PadC22)") (class "Default")
      (node (ref "P1") (pin "C22") (pinfunction "C22_C22") (pintype "passive"))
    )
    (net (code "81") (name "unconnected-(P1-PadC23)") (class "Default")
      (node (ref "P1") (pin "C23") (pinfunction "C23_C23") (pintype "passive"))
    )
    (net (code "82") (name "unconnected-(P1-PadC25)") (class "Default")
      (node (ref "P1") (pin "C25") (pinfunction "C25_C25") (pintype "passive"))
    )
    (net (code "83") (name "unconnected-(P1-PadC26)") (class "Default")
      (node (ref "P1") (pin "C26") (pinfunction "C26_C26") (pintype "passive"))
    )
    (net (code "84") (name "unconnected-(P1-PadC27)") (class "Default")
      (node (ref "P1") (pin "C27") (pinfunction "C27_C27") (pintype "passive"))
    )
    (net (code "85") (name "unconnected-(P1-PadC28)") (class "Default")
      (node (ref "P1") (pin "C28") (pinfunction "C28_C28") (pintype "passive"))
    )
  )
)
